# Center_Console_-_Connectors.net
KiCad netlist of a schematic drawn in Altium Designer
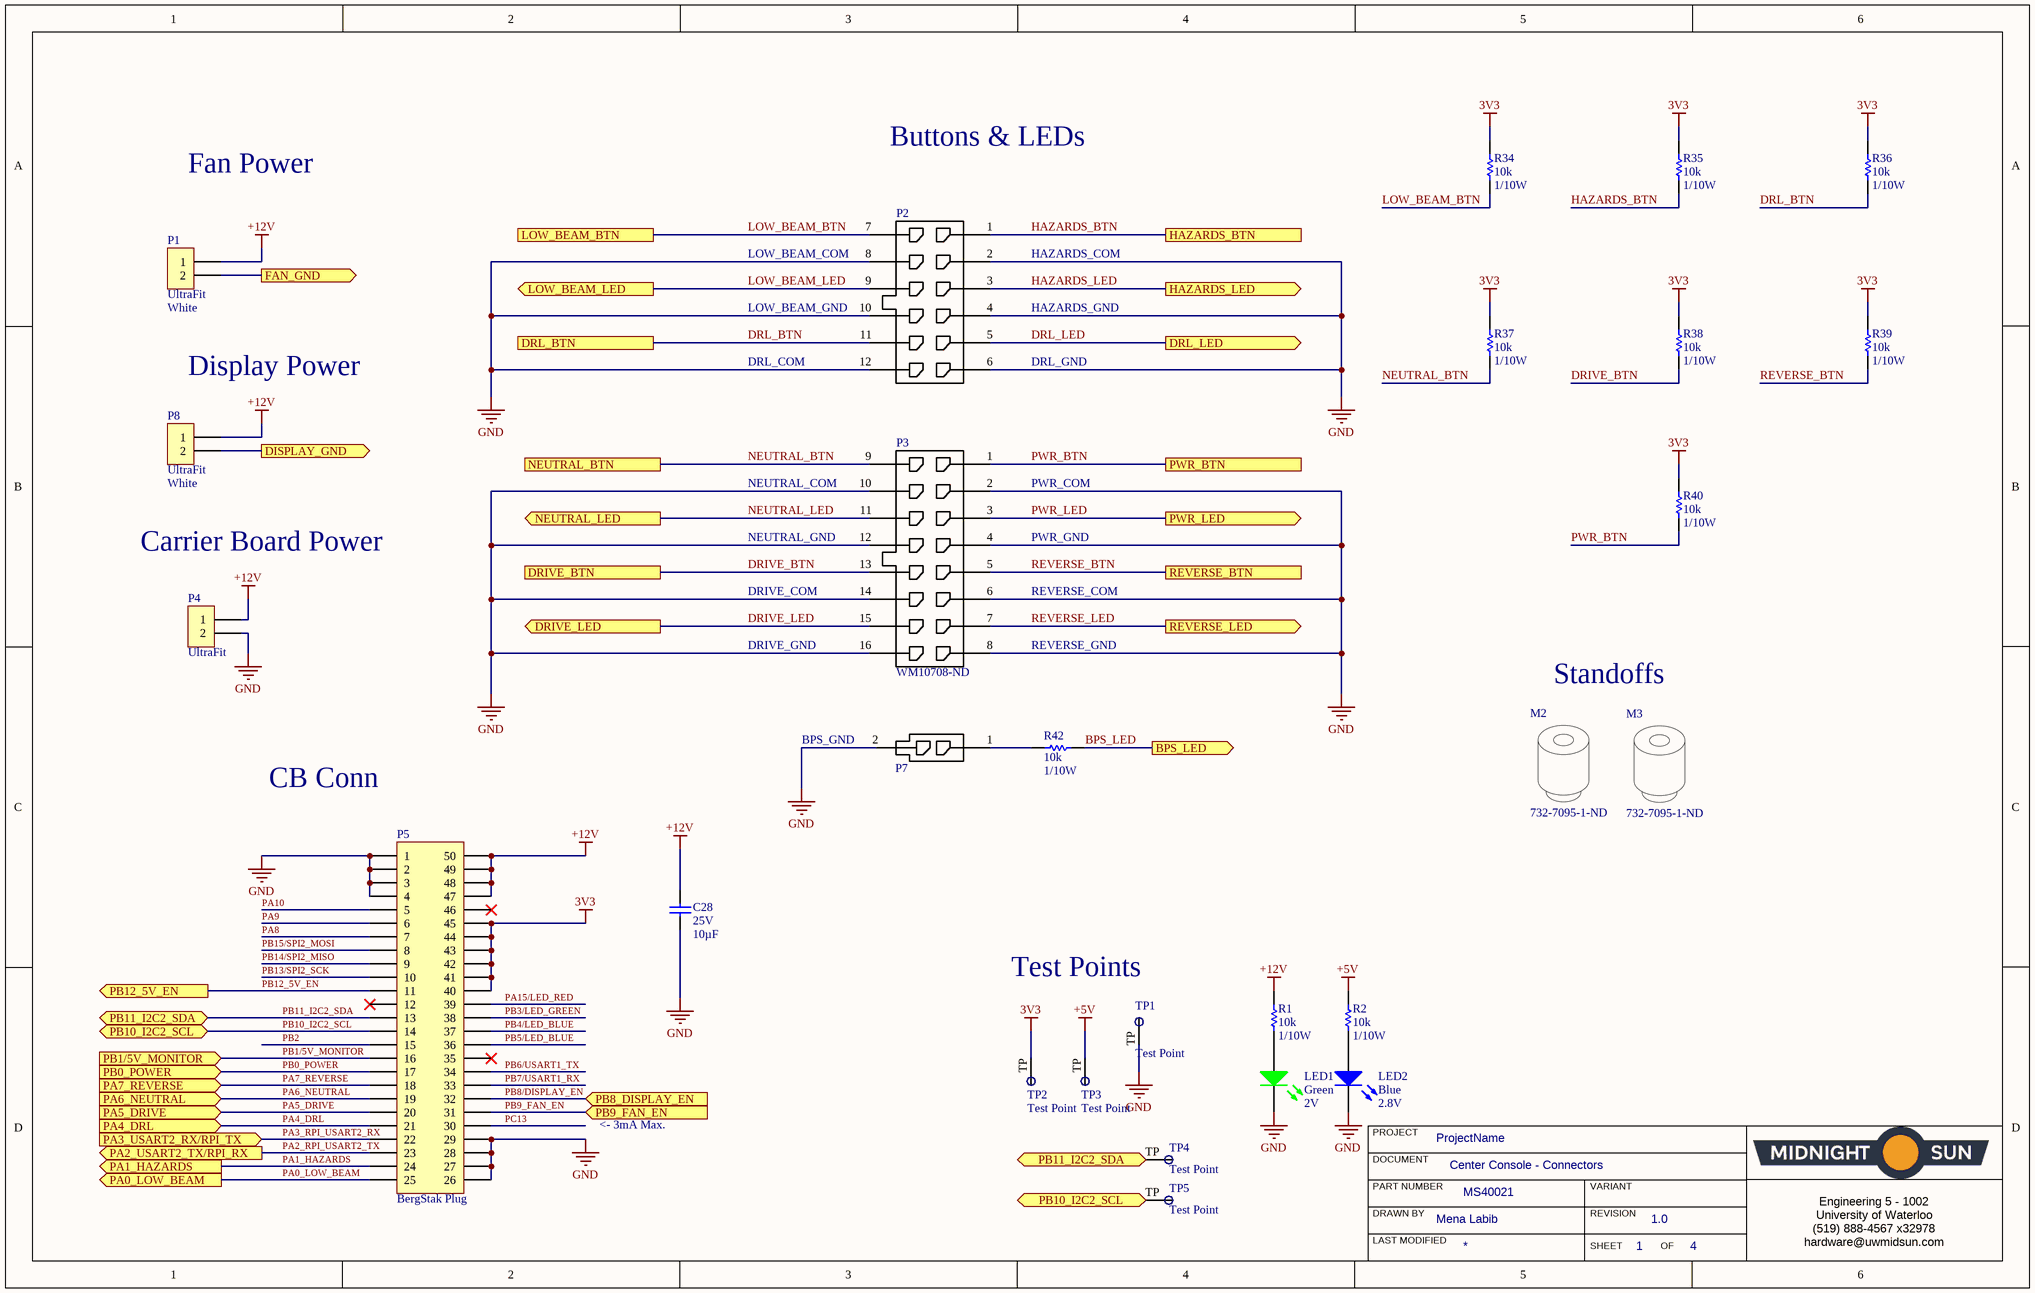
[diagram p0: Center Console - Connectors.SchDoc]

(export (version "E")
  (design (tool "Eeschema 10.0.6"))
  (components
    (comp (ref "C28")
      (value "CAP CER 10uF 25V 10% X5R 0805")
      (footprint "CAP, 0805")
      (description "10µF ±10% 25V Ceramic Capacitor X5R 0805 (2012 Metric)")
      (fields
        (field (name "MANUFACTURER") "Murata Electronics North America")
        (field (name "MANUFACTURER PART NUMBER") "GRM21BR61E106KA73L")
        (field (name "VOLTAGE - RATED") "25V")
        (field (name "CAPACITANCE") "10µF")
      )
      (libsource (lib "altium-import") (part "root_0_CAP CER 10uF 25V 10% X5R 0805_"))
    )
    (comp (ref "LED1")
      (value "LED GREEN CLEAR 2V 0603")
      (footprint "LED_0603")
      (description "Green 572nm LED Indication - Discrete 2V 0603 (1608 Metric)")
      (fields
        (field (name "MANUFACTURER") "Wurth Electronics Inc.")
        (field (name "MANUFACTURER PART NUMBER") "150060VS75000")
        (field (name "COLOR") "Green")
        (field (name "VOLTAGE - FORWARD (VF) (TYP)") "2V")
      )
      (libsource (lib "Schematic Diagrams") (part "LED GREEN CLEAR 2V 0603"))
    )
    (comp (ref "LED2")
      (value "LED BLUE CLEAR 2.8V 0603")
      (footprint "LED_0603")
      (description "Blue 470nm LED Indication - Discrete 2.8V 0603 (1608 Metric)")
      (fields (field (name "COLOR") "Blue") (field (name "VOLTAGE - FORWARD (VF) (TYP)") "2.8V"))
      (libsource (lib "Schematic Diagrams") (part "LED BLUE CLEAR 2.8V 0603"))
    )
    (comp (ref "M2")
      (value "STANDOFF RND M2.5X0.45 STEEL 5MM")
      (footprint "STANDOFF RND M2.5X0.45 STEEL 5MM")
      (fields
        (field (name "MANUFACTURER") "Wurth Electronics")
        (field (name "MANUFACTURER PART NUMBER") "9774050151R")
        (field (name "SUPPLIER PART NUMBER 1") "732-7095-1-ND")
      )
      (libsource (lib "Schematic Diagrams") (part "STANDOFF RND M2.5X0.45 STEEL 5MM"))
    )
    (comp (ref "M3")
      (value "STANDOFF RND M2.5X0.45 STEEL 5MM")
      (footprint "STANDOFF RND M2.5X0.45 STEEL 5MM")
      (fields
        (field (name "MANUFACTURER") "Wurth Electronics")
        (field (name "MANUFACTURER PART NUMBER") "9774050151R")
        (field (name "SUPPLIER PART NUMBER 1") "732-7095-1-ND")
      )
      (libsource (lib "Schematic Diagrams") (part "STANDOFF RND M2.5X0.45 STEEL 5MM"))
    )
    (comp (ref "P1")
      (value "CONN 2POS ULTRA-FIT NATURAL COLOR 0.138\"")
      (footprint "CONN, 2POS ULTRA-FIT - NATURAL COLOR")
      (description "2 Positions Header, Shrouded Connector 0.138\" (3.50mm) Through Hole")
      (fields
        (field (name "VOLTAGE") "400V")
        (field (name "SERIES") "UltraFit")
        (field (name "COLOR") "White")
      )
      (libsource (lib "Schematic Diagrams") (part "CONN 2POS ULTRA-FIT NATURAL COLOR 0.138{dblquote}"))
    )
    (comp (ref "P2")
      (value "CONN 12POS MICRO-FIT 3mm")
      (footprint "CONN, 12POS MICRO-FIT 3mm")
      (description "Connector Header Through Hole 12 position 0.118\" (3.00mm)")
      (fields
        (field (name "MANUFACTURER") "Molex, LLC")
        (field (name "MANUFACTURER PART NUMBER") "0430451227")
      )
      (libsource (lib "Schematic Diagrams") (part "CONN 12POS MICRO-FIT 3mm"))
    )
    (comp (ref "P3")
      (value "CONN 16POS MICRO-FIT 3mm")
      (footprint "Footprints:CONN, 16POS MICRO-FIT 3MM")
      (description "Connector Header Through Hole 16 position 0.118\"(3.00mm)")
      (fields
        (field (name "MANUFACTURER") "Molex")
        (field (name "MANUFACTURER PART NUMBER") "0430451627")
        (field (name "SUPPLIER PART NUMBER 1") "WM10708-ND")
      )
      (libsource (lib "Schematic Diagrams") (part "CONN 16POS MICRO-FIT 3mm"))
    )
    (comp (ref "P4")
      (value "CONN 2POS ULTRA-FIT 0.138\"")
      (footprint "CONN, 2POS ULTRA-FIT")
      (description "2 Positions Header, Shrouded Connector 0.138\" (3.50mm) Through Hole Gold")
      (fields (field (name "VOLTAGE") "400V") (field (name "SERIES") "UltraFit"))
      (libsource (lib "Schematic Diagrams") (part "CONN 2POS ULTRA-FIT 0.138{dblquote}"))
    )
    (comp (ref "P5")
      (value "CONN 50POS Bergstak Plug 0.02\"")
      (footprint "CONN, Bergstak 50 Pos Plug")
      (description "50 Position Connector Plug, Outer Shroud Contacts Surface Mount Gold")
      (fields (field (name "SERIES") "BergStak Plug"))
      (libsource (lib "Schematic Diagrams") (part "CONN 50POS Bergstak Plug 0.02{dblquote}"))
    )
    (comp (ref "P7")
      (value "CONN 2POS MICRO-FIT 3mm")
      (footprint "CONN, 2POS MICRO-FIT")
      (description "Connector Header Through Hole 2 position")
      (fields (field (name "MANUFACTURER") "Molex") (field (name "MANUFACTURER PART NUMBER") "43045-0227"))
      (libsource (lib "Schematic Diagrams") (part "CONN 2POS MICRO-FIT 3mm"))
    )
    (comp (ref "P8")
      (value "CONN 2POS ULTRA-FIT NATURAL COLOR 0.138\"")
      (footprint "CONN, 2POS ULTRA-FIT - NATURAL COLOR")
      (description "2 Positions Header, Shrouded Connector 0.138\" (3.50mm) Through Hole")
      (fields
        (field (name "VOLTAGE") "400V")
        (field (name "SERIES") "UltraFit")
        (field (name "COLOR") "White")
      )
      (libsource (lib "Schematic Diagrams") (part "CONN 2POS ULTRA-FIT NATURAL COLOR 0.138{dblquote}"))
    )
    (comp (ref "R1")
      (value "RES 10K OHM 1% 1/10W 0603")
      (footprint "RES, 0603")
      (description "RES SMD 10K OHM 1% 1/10W 0603")
      (fields
        (field (name "TOLERANCE") "±1%")
        (field (name "RESISTANCE") "10k")
        (field (name "POWER") "1/10W")
      )
      (libsource (lib "Schematic Diagrams") (part "RES 10K OHM 1% 1/10W 0603"))
    )
    (comp (ref "R2")
      (value "RES 10K OHM 1% 1/10W 0603")
      (footprint "RES, 0603")
      (description "RES SMD 10K OHM 1% 1/10W 0603")
      (fields
        (field (name "TOLERANCE") "±1%")
        (field (name "RESISTANCE") "10k")
        (field (name "POWER") "1/10W")
      )
      (libsource (lib "Schematic Diagrams") (part "RES 10K OHM 1% 1/10W 0603"))
    )
    (comp (ref "R34")
      (value "RES 10K OHM 1% 1/10W 0603")
      (footprint "RES, 0603")
      (description "RES SMD 10K OHM 1% 1/10W 0603")
      (fields
        (field (name "TOLERANCE") "±1%")
        (field (name "RESISTANCE") "10k")
        (field (name "POWER") "1/10W")
      )
      (libsource (lib "altium-import") (part "root_0_RES 10K OHM 1% 1/10W 0603_"))
    )
    (comp (ref "R35")
      (value "RES 10K OHM 1% 1/10W 0603")
      (footprint "RES, 0603")
      (description "RES SMD 10K OHM 1% 1/10W 0603")
      (fields
        (field (name "TOLERANCE") "±1%")
        (field (name "RESISTANCE") "10k")
        (field (name "POWER") "1/10W")
      )
      (libsource (lib "altium-import") (part "root_0_RES 10K OHM 1% 1/10W 0603_"))
    )
    (comp (ref "R36")
      (value "RES 10K OHM 1% 1/10W 0603")
      (footprint "RES, 0603")
      (description "RES SMD 10K OHM 1% 1/10W 0603")
      (fields
        (field (name "TOLERANCE") "±1%")
        (field (name "RESISTANCE") "10k")
        (field (name "POWER") "1/10W")
      )
      (libsource (lib "altium-import") (part "root_0_RES 10K OHM 1% 1/10W 0603_"))
    )
    (comp (ref "R37")
      (value "RES 10K OHM 1% 1/10W 0603")
      (footprint "RES, 0603")
      (description "RES SMD 10K OHM 1% 1/10W 0603")
      (fields
        (field (name "TOLERANCE") "±1%")
        (field (name "RESISTANCE") "10k")
        (field (name "POWER") "1/10W")
      )
      (libsource (lib "altium-import") (part "root_0_RES 10K OHM 1% 1/10W 0603_"))
    )
    (comp (ref "R38")
      (value "RES 10K OHM 1% 1/10W 0603")
      (footprint "RES, 0603")
      (description "RES SMD 10K OHM 1% 1/10W 0603")
      (fields
        (field (name "TOLERANCE") "±1%")
        (field (name "RESISTANCE") "10k")
        (field (name "POWER") "1/10W")
      )
      (libsource (lib "altium-import") (part "root_0_RES 10K OHM 1% 1/10W 0603_"))
    )
    (comp (ref "R39")
      (value "RES 10K OHM 1% 1/10W 0603")
      (footprint "RES, 0603")
      (description "RES SMD 10K OHM 1% 1/10W 0603")
      (fields
        (field (name "TOLERANCE") "±1%")
        (field (name "RESISTANCE") "10k")
        (field (name "POWER") "1/10W")
      )
      (libsource (lib "altium-import") (part "root_0_RES 10K OHM 1% 1/10W 0603_"))
    )
    (comp (ref "R40")
      (value "RES 10K OHM 1% 1/10W 0603")
      (footprint "RES, 0603")
      (description "RES SMD 10K OHM 1% 1/10W 0603")
      (fields
        (field (name "TOLERANCE") "±1%")
        (field (name "RESISTANCE") "10k")
        (field (name "POWER") "1/10W")
      )
      (libsource (lib "altium-import") (part "root_0_RES 10K OHM 1% 1/10W 0603_"))
    )
    (comp (ref "R42")
      (value "RES 10K OHM 1% 1/10W 0603")
      (footprint "RES, 0603")
      (description "RES SMD 10K OHM 1% 1/10W 0603")
      (fields
        (field (name "TOLERANCE") "±1%")
        (field (name "RESISTANCE") "10k")
        (field (name "POWER") "1/10W")
      )
      (libsource (lib "altium-import") (part "root_1_RES 10K OHM 1% 1/10W 0603_"))
    )
    (comp (ref "TP1")
      (value "Test Point")
      (footprint "Test Point")
      (libsource (lib "Schematic Diagrams") (part "Test Point"))
    )
    (comp (ref "TP2")
      (value "Test Point")
      (footprint "Test Point")
      (libsource (lib "Schematic Diagrams") (part "Test Point"))
    )
    (comp (ref "TP3")
      (value "Test Point")
      (footprint "Test Point")
      (libsource (lib "Schematic Diagrams") (part "Test Point"))
    )
    (comp (ref "TP4")
      (value "Test Point")
      (footprint "Test Point")
      (libsource (lib "Schematic Diagrams") (part "Test Point"))
    )
    (comp (ref "TP5")
      (value "Test Point")
      (footprint "Test Point")
      (libsource (lib "Schematic Diagrams") (part "Test Point"))
    )
  )
  (nets
    (net (code "1") (name "+5V") (class "Default")
      (node (ref "R2") (pin "1") (pinfunction "1_1") (pintype "passive"))
      (node (ref "TP3") (pin "TP") (pinfunction "1_TP") (pintype "passive"))
    )
    (net (code "2") (name "+12V") (class "Default")
      (node (ref "C28") (pin "1") (pinfunction "1_1") (pintype "passive"))
      (node (ref "P1") (pin "1") (pinfunction "1_1") (pintype "passive"))
      (node (ref "P4") (pin "1") (pinfunction "1_1") (pintype "passive"))
      (node (ref "P5") (pin "47") (pinfunction "47_47") (pintype "passive"))
      (node (ref "P5") (pin "48") (pinfunction "48_48") (pintype "passive"))
      (node (ref "P5") (pin "49") (pinfunction "49_49") (pintype "passive"))
      (node (ref "P5") (pin "50") (pinfunction "50_50") (pintype "passive"))
      (node (ref "P8") (pin "1") (pinfunction "1_1") (pintype "passive"))
      (node (ref "R1") (pin "1") (pinfunction "1_1") (pintype "passive"))
    )
    (net (code "3") (name "/BPS_LED") (class "Default")
      (node (ref "R42") (pin "2") (pinfunction "2_2") (pintype "passive"))
    )
    (net (code "4") (name "/DISPLAY_GND") (class "Default")
      (node (ref "P8") (pin "2") (pinfunction "2_2") (pintype "passive"))
    )
    (net (code "5") (name "/DRIVE_BTN") (class "Default")
      (node (ref "P3") (pin "13") (pinfunction "13_13") (pintype "passive"))
      (node (ref "R38") (pin "2") (pinfunction "2_2") (pintype "passive"))
    )
    (net (code "6") (name "/DRIVE_LED") (class "Default")
      (node (ref "P3") (pin "15") (pinfunction "15_15") (pintype "passive"))
    )
    (net (code "7") (name "/DRL_BTN") (class "Default")
      (node (ref "P2") (pin "11") (pinfunction "11_11") (pintype "passive"))
      (node (ref "R36") (pin "2") (pinfunction "2_2") (pintype "passive"))
    )
    (net (code "8") (name "/DRL_LED") (class "Default")
      (node (ref "P2") (pin "5") (pinfunction "5_5") (pintype "passive"))
    )
    (net (code "9") (name "/FAN_GND") (class "Default")
      (node (ref "P1") (pin "2") (pinfunction "2_2") (pintype "passive"))
    )
    (net (code "10") (name "/HAZARDS_BTN") (class "Default")
      (node (ref "P2") (pin "1") (pinfunction "1_1") (pintype "passive"))
      (node (ref "R35") (pin "2") (pinfunction "2_2") (pintype "passive"))
    )
    (net (code "11") (name "/HAZARDS_LED") (class "Default")
      (node (ref "P2") (pin "3") (pinfunction "3_3") (pintype "passive"))
    )
    (net (code "12") (name "/LOW_BEAM_BTN") (class "Default")
      (node (ref "P2") (pin "7") (pinfunction "7_7") (pintype "passive"))
      (node (ref "R34") (pin "2") (pinfunction "2_2") (pintype "passive"))
    )
    (net (code "13") (name "/LOW_BEAM_LED") (class "Default")
      (node (ref "P2") (pin "9") (pinfunction "9_9") (pintype "passive"))
    )
    (net (code "14") (name "/NEUTRAL_BTN") (class "Default")
      (node (ref "P3") (pin "9") (pinfunction "9_9") (pintype "passive"))
      (node (ref "R37") (pin "2") (pinfunction "2_2") (pintype "passive"))
    )
    (net (code "15") (name "/NEUTRAL_LED") (class "Default")
      (node (ref "P3") (pin "11") (pinfunction "11_11") (pintype "passive"))
    )
    (net (code "16") (name "/PA0_LOW_BEAM") (class "Default")
      (node (ref "P5") (pin "25") (pinfunction "25_25") (pintype "passive"))
    )
    (net (code "17") (name "/PA1_HAZARDS") (class "Default")
      (node (ref "P5") (pin "24") (pinfunction "24_24") (pintype "passive"))
    )
    (net (code "18") (name "/PA2_RPI_USART2_TX") (class "Default")
      (node (ref "P5") (pin "23") (pinfunction "23_23") (pintype "passive"))
    )
    (net (code "19") (name "/PA3_RPI_USART2_RX") (class "Default")
      (node (ref "P5") (pin "22") (pinfunction "22_22") (pintype "passive"))
    )
    (net (code "20") (name "/PA4_DRL") (class "Default")
      (node (ref "P5") (pin "21") (pinfunction "21_21") (pintype "passive"))
    )
    (net (code "21") (name "/PA5_DRIVE") (class "Default")
      (node (ref "P5") (pin "20") (pinfunction "20_20") (pintype "passive"))
    )
    (net (code "22") (name "/PA6_NEUTRAL") (class "Default")
      (node (ref "P5") (pin "19") (pinfunction "19_19") (pintype "passive"))
    )
    (net (code "23") (name "/PA7_REVERSE") (class "Default")
      (node (ref "P5") (pin "18") (pinfunction "18_18") (pintype "passive"))
    )
    (net (code "24") (name "/PA8") (class "Default")
      (node (ref "P5") (pin "7") (pinfunction "7_7") (pintype "passive"))
    )
    (net (code "25") (name "/PA9") (class "Default")
      (node (ref "P5") (pin "6") (pinfunction "6_6") (pintype "passive"))
    )
    (net (code "26") (name "/PA10") (class "Default")
      (node (ref "P5") (pin "5") (pinfunction "5_5") (pintype "passive"))
    )
    (net (code "27") (name "/PA15{slash}LED_RED") (class "Default")
      (node (ref "P5") (pin "39") (pinfunction "39_39") (pintype "passive"))
    )
    (net (code "28") (name "/PB0_POWER") (class "Default")
      (node (ref "P5") (pin "17") (pinfunction "17_17") (pintype "passive"))
    )
    (net (code "29") (name "/PB1{slash}5V_MONITOR") (class "Default")
      (node (ref "P5") (pin "16") (pinfunction "16_16") (pintype "passive"))
    )
    (net (code "30") (name "/PB2") (class "Default")
      (node (ref "P5") (pin "15") (pinfunction "15_15") (pintype "passive"))
    )
    (net (code "31") (name "/PB3{slash}LED_GREEN") (class "Default")
      (node (ref "P5") (pin "38") (pinfunction "38_38") (pintype "passive"))
    )
    (net (code "32") (name "/PB4{slash}LED_BLUE") (class "Default")
      (node (ref "P5") (pin "37") (pinfunction "37_37") (pintype "passive"))
    )
    (net (code "33") (name "/PB5{slash}LED_BLUE") (class "Default")
      (node (ref "P5") (pin "36") (pinfunction "36_36") (pintype "passive"))
    )
    (net (code "34") (name "/PB6{slash}USART1_TX") (class "Default")
      (node (ref "P5") (pin "34") (pinfunction "34_34") (pintype "passive"))
    )
    (net (code "35") (name "/PB7{slash}USART1_RX") (class "Default")
      (node (ref "P5") (pin "33") (pinfunction "33_33") (pintype "passive"))
    )
    (net (code "36") (name "/PB8{slash}DISPLAY_EN") (class "Default")
      (node (ref "P5") (pin "32") (pinfunction "32_32") (pintype "passive"))
    )
    (net (code "37") (name "/PB9_FAN_EN") (class "Default")
      (node (ref "P5") (pin "31") (pinfunction "31_31") (pintype "passive"))
    )
    (net (code "38") (name "/PB10_I2C2_SCL") (class "Default")
      (node (ref "P5") (pin "14") (pinfunction "14_14") (pintype "passive"))
      (node (ref "TP5") (pin "TP") (pinfunction "1_TP") (pintype "passive"))
    )
    (net (code "39") (name "/PB11_I2C2_SDA") (class "Default")
      (node (ref "P5") (pin "13") (pinfunction "13_13") (pintype "passive"))
      (node (ref "TP4") (pin "TP") (pinfunction "1_TP") (pintype "passive"))
    )
    (net (code "40") (name "/PB12_5V_EN") (class "Default")
      (node (ref "P5") (pin "11") (pinfunction "11_11") (pintype "passive"))
    )
    (net (code "41") (name "/PB13{slash}SPI2_SCK") (class "Default")
      (node (ref "P5") (pin "10") (pinfunction "10_10") (pintype "passive"))
    )
    (net (code "42") (name "/PB14{slash}SPI2_MISO") (class "Default")
      (node (ref "P5") (pin "9") (pinfunction "9_9") (pintype "passive"))
    )
    (net (code "43") (name "/PB15{slash}SPI2_MOSI") (class "Default")
      (node (ref "P5") (pin "8") (pinfunction "8_8") (pintype "passive"))
    )
    (net (code "44") (name "/PC13") (class "Default")
      (node (ref "P5") (pin "30") (pinfunction "30_30") (pintype "passive"))
    )
    (net (code "45") (name "/PWR_BTN") (class "Default")
      (node (ref "P3") (pin "1") (pinfunction "1_1") (pintype "passive"))
      (node (ref "R40") (pin "2") (pinfunction "2_2") (pintype "passive"))
    )
    (net (code "46") (name "/PWR_LED") (class "Default")
      (node (ref "P3") (pin "3") (pinfunction "3_3") (pintype "passive"))
    )
    (net (code "47") (name "/REVERSE_BTN") (class "Default")
      (node (ref "P3") (pin "5") (pinfunction "5_5") (pintype "passive"))
      (node (ref "R39") (pin "2") (pinfunction "2_2") (pintype "passive"))
    )
    (net (code "48") (name "/REVERSE_LED") (class "Default")
      (node (ref "P3") (pin "7") (pinfunction "7_7") (pintype "passive"))
    )
    (net (code "49") (name "3V3") (class "Default")
      (node (ref "P5") (pin "40") (pinfunction "40_40") (pintype "passive"))
      (node (ref "P5") (pin "41") (pinfunction "41_41") (pintype "passive"))
      (node (ref "P5") (pin "42") (pinfunction "42_42") (pintype "passive"))
      (node (ref "P5") (pin "43") (pinfunction "43_43") (pintype "passive"))
      (node (ref "P5") (pin "44") (pinfunction "44_44") (pintype "passive"))
      (node (ref "P5") (pin "45") (pinfunction "45_45") (pintype "passive"))
      (node (ref "R34") (pin "1") (pinfunction "1_1") (pintype "passive"))
      (node (ref "R35") (pin "1") (pinfunction "1_1") (pintype "passive"))
      (node (ref "R36") (pin "1") (pinfunction "1_1") (pintype "passive"))
      (node (ref "R37") (pin "1") (pinfunction "1_1") (pintype "passive"))
      (node (ref "R38") (pin "1") (pinfunction "1_1") (pintype "passive"))
      (node (ref "R39") (pin "1") (pinfunction "1_1") (pintype "passive"))
      (node (ref "R40") (pin "1") (pinfunction "1_1") (pintype "passive"))
      (node (ref "TP2") (pin "TP") (pinfunction "1_TP") (pintype "passive"))
    )
    (net (code "50") (name "GND") (class "Default")
      (node (ref "C28") (pin "2") (pinfunction "2_2") (pintype "passive"))
      (node (ref "LED1") (pin "2") (pinfunction "K_2") (pintype "passive"))
      (node (ref "LED2") (pin "2") (pinfunction "K_2") (pintype "passive"))
      (node (ref "P2") (pin "10") (pinfunction "10_10") (pintype "passive"))
      (node (ref "P2") (pin "12") (pinfunction "12_12") (pintype "passive"))
      (node (ref "P2") (pin "2") (pinfunction "2_2") (pintype "passive"))
      (node (ref "P2") (pin "4") (pinfunction "4_4") (pintype "passive"))
      (node (ref "P2") (pin "6") (pinfunction "6_6") (pintype "passive"))
      (node (ref "P2") (pin "8") (pinfunction "8_8") (pintype "passive"))
      (node (ref "P3") (pin "10") (pinfunction "10_10") (pintype "passive"))
      (node (ref "P3") (pin "12") (pinfunction "12_12") (pintype "passive"))
      (node (ref "P3") (pin "14") (pinfunction "14_14") (pintype "passive"))
      (node (ref "P3") (pin "16") (pinfunction "16_16") (pintype "passive"))
      (node (ref "P3") (pin "2") (pinfunction "2_2") (pintype "passive"))
      (node (ref "P3") (pin "4") (pinfunction "4_4") (pintype "passive"))
      (node (ref "P3") (pin "6") (pinfunction "6_6") (pintype "passive"))
      (node (ref "P3") (pin "8") (pinfunction "8_8") (pintype "passive"))
      (node (ref "P4") (pin "2") (pinfunction "2_2") (pintype "passive"))
      (node (ref "P5") (pin "1") (pinfunction "1_1") (pintype "passive"))
      (node (ref "P5") (pin "2") (pinfunction "2_2") (pintype "passive"))
      (node (ref "P5") (pin "26") (pinfunction "26_26") (pintype "passive"))
      (node (ref "P5") (pin "27") (pinfunction "27_27") (pintype "passive"))
      (node (ref "P5") (pin "28") (pinfunction "28_28") (pintype "passive"))
      (node (ref "P5") (pin "29") (pinfunction "29_29") (pintype "passive"))
      (node (ref "P5") (pin "3") (pinfunction "3_3") (pintype "passive"))
      (node (ref "P5") (pin "4") (pinfunction "4_4") (pintype "passive"))
      (node (ref "P7") (pin "2") (pinfunction "2_2") (pintype "passive"))
      (node (ref "TP1") (pin "TP") (pinfunction "1_TP") (pintype "passive"))
    )
    (net (code "51") (name "Net-(LED1-A)") (class "Default")
      (node (ref "LED1") (pin "1") (pinfunction "A_1") (pintype "passive"))
      (node (ref "R1") (pin "2") (pinfunction "2_2") (pintype "passive"))
    )
    (net (code "52") (name "Net-(LED2-A)") (class "Default")
      (node (ref "LED2") (pin "1") (pinfunction "A_1") (pintype "passive"))
      (node (ref "R2") (pin "2") (pinfunction "2_2") (pintype "passive"))
    )
    (net (code "53") (name "Net-(P7-Pad1)") (class "Default")
      (node (ref "P7") (pin "1") (pinfunction "1_1") (pintype "passive"))
      (node (ref "R42") (pin "1") (pinfunction "1_1") (pintype "passive"))
    )
    (net (code "54") (name "unconnected-(P5-Pad12)") (class "Default")
      (node (ref "P5") (pin "12") (pinfunction "12_12") (pintype "passive+no_connect"))
    )
    (net (code "55") (name "unconnected-(P5-Pad35)") (class "Default")
      (node (ref "P5") (pin "35") (pinfunction "35_35") (pintype "passive+no_connect"))
    )
    (net (code "56") (name "unconnected-(P5-Pad46)") (class "Default")
      (node (ref "P5") (pin "46") (pinfunction "46_46") (pintype "passive+no_connect"))
    )
  )
)
